# schema.net
KiCad netlist of a schematic drawn in EAGLE
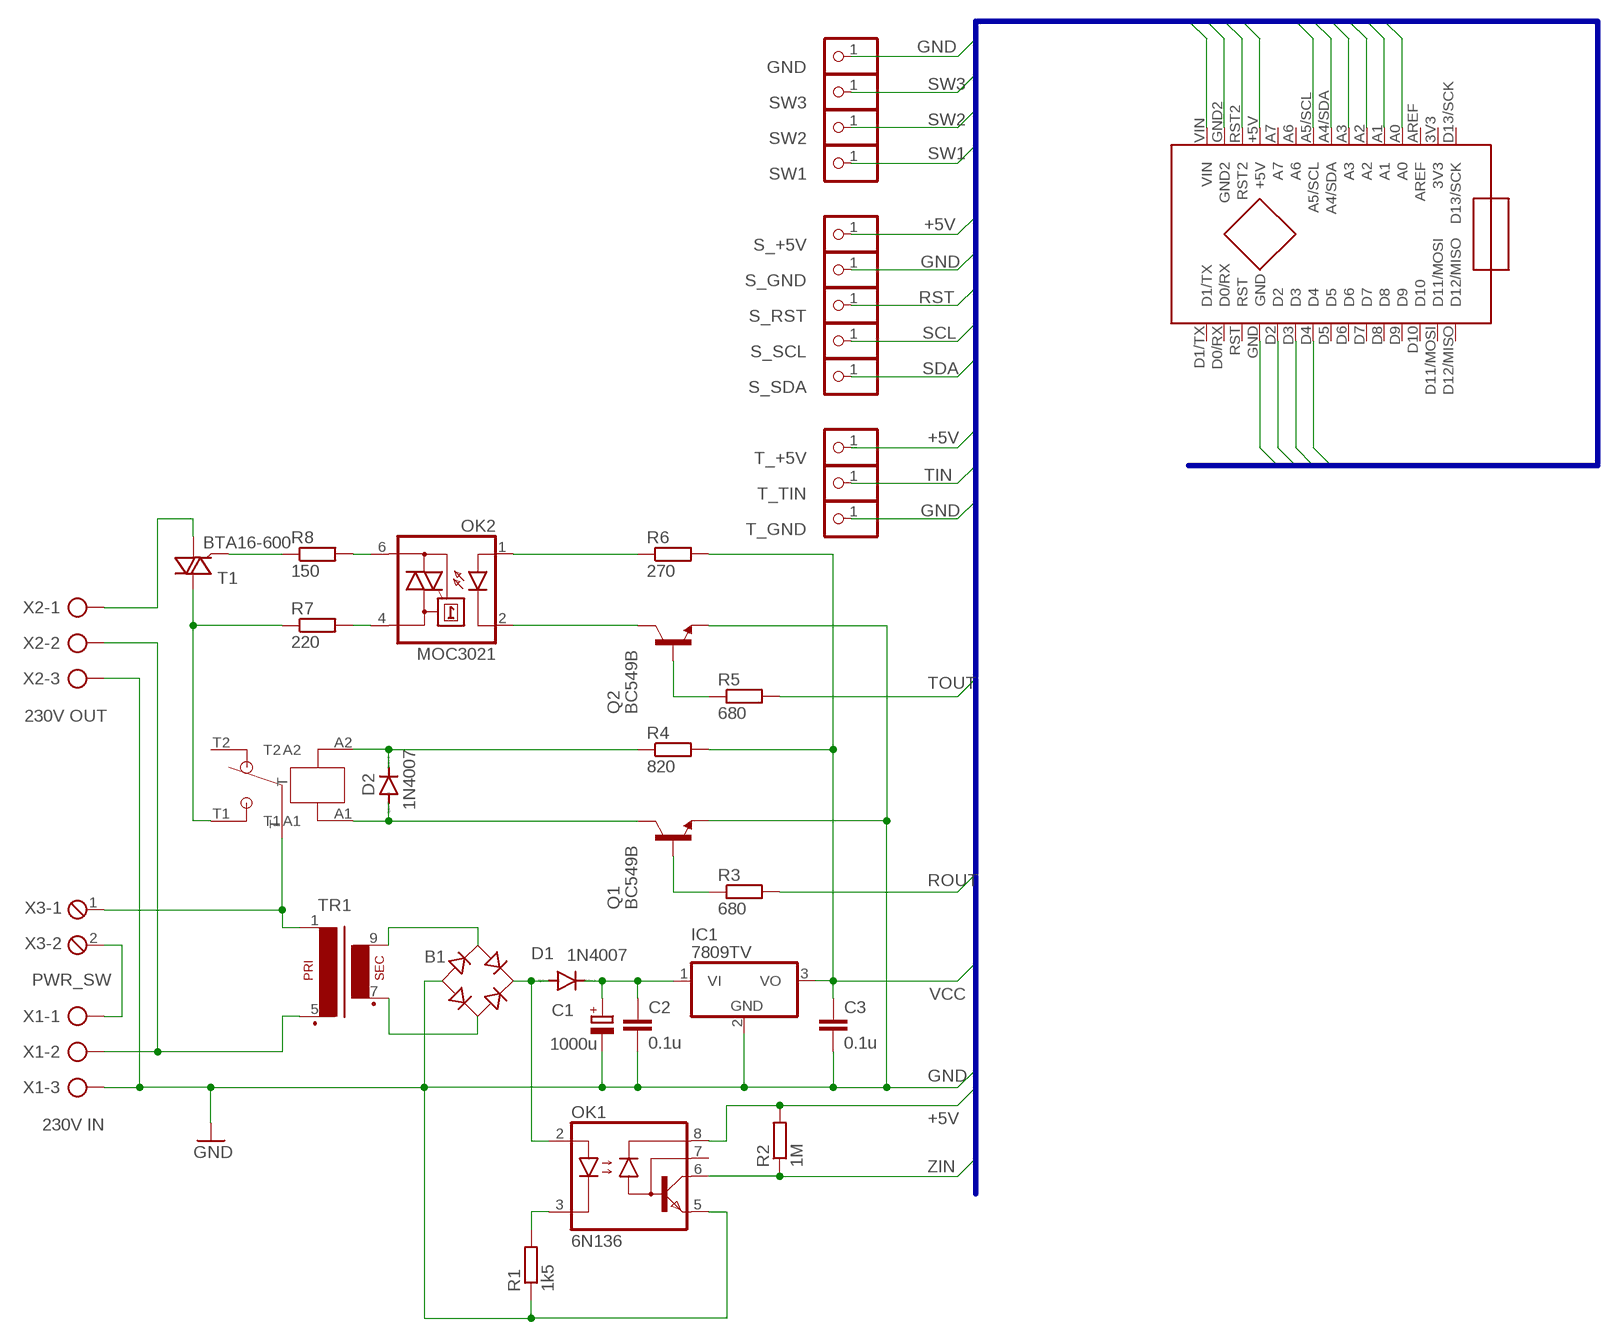
[diagram p0: schematic, sheet 1]

(export (version "E")
  (design (tool "Eeschema 10.0.6"))
  (components
    (comp (ref "B1")
      (value "B-DIL")
      (footprint "eagle-import:B-DIL")
      (libsource (lib "eagle-import") (part "B-DIL"))
    )
    (comp (ref "C1")
      (value "1000u")
      (footprint "eagle-import:E5-8,5")
      (libsource (lib "eagle-import") (part "CPOL-EUE5-8.5"))
    )
    (comp (ref "C2")
      (value "0.1u")
      (footprint "eagle-import:C050-024X044")
      (libsource (lib "eagle-import") (part "C-EU050-024X044"))
    )
    (comp (ref "C3")
      (value "0.1u")
      (footprint "eagle-import:C050-024X044")
      (libsource (lib "eagle-import") (part "C-EU050-024X044"))
    )
    (comp (ref "D1")
      (value "1N4007")
      (footprint "eagle-import:DO35-7")
      (libsource (lib "eagle-import") (part "1N4148DO35-7"))
    )
    (comp (ref "D2")
      (value "1N4007")
      (footprint "eagle-import:DO35-7")
      (libsource (lib "eagle-import") (part "1N4148DO35-7"))
    )
    (comp (ref "GND")
      (value "PINHD-1X1")
      (footprint "eagle-import:1X01")
      (libsource (lib "eagle-import") (part "PINHD-1X1"))
    )
    (comp (ref "IC1")
      (value "7809TV")
      (footprint "eagle-import:TO220V")
      (libsource (lib "eagle-import") (part "78TV05"))
    )
    (comp (ref "OK1")
      (value "6N136")
      (footprint "eagle-import:DIL08")
      (fields (field (name "MF") "FAIRCHILD SEMICONDUCTOR") (field (name "MPN") "6N135"))
      (libsource (lib "eagle-import") (part "6N135"))
    )
    (comp (ref "OK2")
      (value "MOC3021")
      (footprint "eagle-import:DIL06")
      (fields
        (field (name "MF") "FAIRCHILD SEMICONDUCTOR")
        (field (name "MPN") "MOC3041M")
        (field (name "MPN_1") "MOC3021")
      )
      (libsource (lib "eagle-import") (part "MOC3041M"))
    )
    (comp (ref "Q1")
      (value "BC549B")
      (footprint "eagle-import:TO92-EBC")
      (libsource (lib "eagle-import") (part "BC549B"))
    )
    (comp (ref "Q2")
      (value "BC549B")
      (footprint "eagle-import:TO92-EBC")
      (libsource (lib "eagle-import") (part "BC549B"))
    )
    (comp (ref "R1")
      (value "1k5")
      (footprint "eagle-import:0204V")
      (libsource (lib "eagle-import") (part "R-EU_0204/2V"))
    )
    (comp (ref "R2")
      (value "1M")
      (footprint "eagle-import:0204_5")
      (libsource (lib "eagle-import") (part "R-EU_0204/5"))
    )
    (comp (ref "R3")
      (value "680")
      (footprint "eagle-import:0204_7")
      (libsource (lib "eagle-import") (part "R-EU_0204/7"))
    )
    (comp (ref "R4")
      (value "820")
      (footprint "eagle-import:0204_7")
      (libsource (lib "eagle-import") (part "R-EU_0204/7"))
    )
    (comp (ref "R5")
      (value "680")
      (footprint "eagle-import:0204_7")
      (libsource (lib "eagle-import") (part "R-EU_0204/7"))
    )
    (comp (ref "R6")
      (value "270")
      (footprint "eagle-import:0204_7")
      (libsource (lib "eagle-import") (part "R-EU_0204/7"))
    )
    (comp (ref "R7")
      (value "220")
      (footprint "eagle-import:0204_7")
      (libsource (lib "eagle-import") (part "R-EU_0204/7"))
    )
    (comp (ref "R8")
      (value "150")
      (footprint "eagle-import:0204_7")
      (libsource (lib "eagle-import") (part "R-EU_0204/7"))
    )
    (comp (ref "SW1")
      (value "PINHD-1X1")
      (footprint "eagle-import:1X01")
      (libsource (lib "eagle-import") (part "PINHD-1X1"))
    )
    (comp (ref "SW2")
      (value "PINHD-1X1")
      (footprint "eagle-import:1X01")
      (libsource (lib "eagle-import") (part "PINHD-1X1"))
    )
    (comp (ref "SW3")
      (value "PINHD-1X1")
      (footprint "eagle-import:1X01")
      (libsource (lib "eagle-import") (part "PINHD-1X1"))
    )
    (comp (ref "S_+5V")
      (value "PINHD-1X1")
      (footprint "eagle-import:1X01")
      (libsource (lib "eagle-import") (part "PINHD-1X1"))
    )
    (comp (ref "S_GND")
      (value "PINHD-1X1")
      (footprint "eagle-import:1X01")
      (libsource (lib "eagle-import") (part "PINHD-1X1"))
    )
    (comp (ref "S_RST")
      (value "PINHD-1X1")
      (footprint "eagle-import:1X01")
      (libsource (lib "eagle-import") (part "PINHD-1X1"))
    )
    (comp (ref "S_SCL")
      (value "PINHD-1X1")
      (footprint "eagle-import:1X01")
      (libsource (lib "eagle-import") (part "PINHD-1X1"))
    )
    (comp (ref "S_SDA")
      (value "PINHD-1X1")
      (footprint "eagle-import:1X01")
      (libsource (lib "eagle-import") (part "PINHD-1X1"))
    )
    (comp (ref "T1")
      (value "BTA16-600")
      (footprint "eagle-import:TO220BV")
      (libsource (lib "eagle-import") (part "BT138-V"))
    )
    (comp (ref "TR1")
      (value "EI30-1")
      (footprint "eagle-import:EI30-1")
      (libsource (lib "eagle-import") (part "EI30-1"))
    )
    (comp (ref "T_+5V")
      (value "PINHD-1X1")
      (footprint "eagle-import:1X01")
      (libsource (lib "eagle-import") (part "PINHD-1X1"))
    )
    (comp (ref "T_GND")
      (value "PINHD-1X1")
      (footprint "eagle-import:1X01")
      (libsource (lib "eagle-import") (part "PINHD-1X1"))
    )
    (comp (ref "T_TIN")
      (value "PINHD-1X1")
      (footprint "eagle-import:1X01")
      (libsource (lib "eagle-import") (part "PINHD-1X1"))
    )
    (comp (ref "U$1")
      (value "FINDER_31.21.X")
      (footprint "eagle-import:FINDER_32.21.X")
      (libsource (lib "eagle-import") (part "FINDER_31.21.X"))
    )
    (comp (ref "U$2")
      (value "ARDUINO_NANO")
      (footprint "eagle-import:ARDUINO_NANO")
      (libsource (lib "eagle-import") (part "ARDUINO_NANO"))
    )
    (comp (ref "X1")
      (value "230V IN")
      (footprint "eagle-import:AK500_3")
      (libsource (lib "eagle-import") (part "AK500/3"))
    )
    (comp (ref "X2")
      (value "230V OUT")
      (footprint "eagle-import:AK500_3")
      (libsource (lib "eagle-import") (part "AK500/3"))
    )
    (comp (ref "X3")
      (value "PWR_SW")
      (footprint "eagle-import:2POL254")
      (libsource (lib "eagle-import") (part "MPT2"))
    )
  )
  (nets
    (net (code "1") (name "/+5V") (class "Default")
      (node (ref "OK1") (pin "8") (pinfunction "VCC_8") (pintype "passive"))
      (node (ref "R2") (pin "2") (pinfunction "2_2") (pintype "passive"))
      (node (ref "S_+5V") (pin "1") (pinfunction "1_1") (pintype "passive"))
      (node (ref "T_+5V") (pin "1") (pinfunction "1_1") (pintype "passive"))
      (node (ref "U$2") (pin "+5V") (pinfunction "+5V_+5V") (pintype "bidirectional"))
    )
    (net (code "2") (name "/ROUT") (class "Default")
      (node (ref "R3") (pin "2") (pinfunction "2_2") (pintype "passive"))
      (node (ref "U$2") (pin "A1") (pinfunction "A1_A1") (pintype "bidirectional"))
    )
    (net (code "3") (name "/RST") (class "Default")
      (node (ref "S_RST") (pin "1") (pinfunction "1_1") (pintype "passive"))
      (node (ref "U$2") (pin "RST2") (pinfunction "RST2_RST2") (pintype "bidirectional"))
    )
    (net (code "4") (name "/SCL") (class "Default")
      (node (ref "S_SCL") (pin "1") (pinfunction "1_1") (pintype "passive"))
      (node (ref "U$2") (pin "A5/SCL") (pinfunction "A5/SCL_A5/SCL") (pintype "bidirectional"))
    )
    (net (code "5") (name "/SDA") (class "Default")
      (node (ref "S_SDA") (pin "1") (pinfunction "1_1") (pintype "passive"))
      (node (ref "U$2") (pin "A4/SDA") (pinfunction "A4/SDA_A4/SDA") (pintype "bidirectional"))
    )
    (net (code "6") (name "/SW1") (class "Default")
      (node (ref "SW1") (pin "1") (pinfunction "1_1") (pintype "passive"))
      (node (ref "U$2") (pin "D2") (pinfunction "D2_D2") (pintype "bidirectional"))
    )
    (net (code "7") (name "/SW2") (class "Default")
      (node (ref "SW2") (pin "1") (pinfunction "1_1") (pintype "passive"))
      (node (ref "U$2") (pin "D3") (pinfunction "D3_D3") (pintype "bidirectional"))
    )
    (net (code "8") (name "/SW3") (class "Default")
      (node (ref "SW3") (pin "1") (pinfunction "1_1") (pintype "passive"))
      (node (ref "U$2") (pin "D4") (pinfunction "D4_D4") (pintype "bidirectional"))
    )
    (net (code "9") (name "/TIN") (class "Default")
      (node (ref "T_TIN") (pin "1") (pinfunction "1_1") (pintype "passive"))
      (node (ref "U$2") (pin "A2") (pinfunction "A2_A2") (pintype "bidirectional"))
    )
    (net (code "10") (name "/TOUT") (class "Default")
      (node (ref "R5") (pin "2") (pinfunction "2_2") (pintype "passive"))
      (node (ref "U$2") (pin "A0") (pinfunction "A0_A0") (pintype "bidirectional"))
    )
    (net (code "11") (name "/VCC") (class "Default")
      (node (ref "C3") (pin "1") (pinfunction "1_1") (pintype "passive"))
      (node (ref "IC1") (pin "3") (pinfunction "VO_3") (pintype "passive"))
      (node (ref "R4") (pin "2") (pinfunction "2_2") (pintype "passive"))
      (node (ref "R6") (pin "2") (pinfunction "2_2") (pintype "passive"))
      (node (ref "U$2") (pin "VIN") (pinfunction "VIN_VIN") (pintype "bidirectional"))
    )
    (net (code "12") (name "/ZIN") (class "Default")
      (node (ref "OK1") (pin "6") (pinfunction "VO_6") (pintype "passive"))
      (node (ref "R2") (pin "1") (pinfunction "1_1") (pintype "passive"))
      (node (ref "U$2") (pin "A3") (pinfunction "A3_A3") (pintype "bidirectional"))
    )
    (net (code "13") (name "GND") (class "Default")
      (node (ref "B1") (pin "-") (pinfunction "-_-") (pintype "passive"))
      (node (ref "C1") (pin "-") (pinfunction "-_-") (pintype "passive"))
      (node (ref "C2") (pin "2") (pinfunction "2_2") (pintype "passive"))
      (node (ref "C3") (pin "2") (pinfunction "2_2") (pintype "passive"))
      (node (ref "GND") (pin "1") (pinfunction "1_1") (pintype "passive"))
      (node (ref "IC1") (pin "2") (pinfunction "GND_2") (pintype "passive"))
      (node (ref "OK1") (pin "5") (pinfunction "GND_5") (pintype "passive"))
      (node (ref "Q1") (pin "E") (pinfunction "E_E") (pintype "passive"))
      (node (ref "Q2") (pin "E") (pinfunction "E_E") (pintype "passive"))
      (node (ref "R1") (pin "1") (pinfunction "1_1") (pintype "passive"))
      (node (ref "S_GND") (pin "1") (pinfunction "1_1") (pintype "passive"))
      (node (ref "T_GND") (pin "1") (pinfunction "1_1") (pintype "passive"))
      (node (ref "U$2") (pin "GND") (pinfunction "GND_GND") (pintype "bidirectional"))
      (node (ref "U$2") (pin "GND2") (pinfunction "GND2_GND2") (pintype "bidirectional"))
      (node (ref "X1") (pin "3") (pinfunction "KL_3") (pintype "passive"))
      (node (ref "X2") (pin "3") (pinfunction "KL_3") (pintype "passive"))
    )
    (net (code "14") (name "Net-(D2-PadA)") (class "Default")
      (node (ref "D2") (pin "A") (pinfunction "A_A") (pintype "passive"))
      (node (ref "Q1") (pin "C") (pinfunction "C_C") (pintype "passive"))
      (node (ref "U$1") (pin "A1") (pinfunction "A1_A1") (pintype "bidirectional"))
    )
    (net (code "15") (name "Net-(D2-PadC)") (class "Default")
      (node (ref "D2") (pin "C") (pinfunction "C_C") (pintype "passive"))
      (node (ref "R4") (pin "1") (pinfunction "1_1") (pintype "passive"))
      (node (ref "U$1") (pin "A2") (pinfunction "A2_A2") (pintype "bidirectional"))
    )
    (net (code "16") (name "Net-(IC1-VI)") (class "Default")
      (node (ref "C1") (pin "+") (pinfunction "+_+") (pintype "passive"))
      (node (ref "C2") (pin "1") (pinfunction "1_1") (pintype "passive"))
      (node (ref "D1") (pin "C") (pinfunction "C_C") (pintype "passive"))
      (node (ref "IC1") (pin "1") (pinfunction "VI_1") (pintype "input"))
    )
    (net (code "17") (name "Net-(OK1-A)") (class "Default")
      (node (ref "B1") (pin "+") (pinfunction "+_+") (pintype "passive"))
      (node (ref "D1") (pin "A") (pinfunction "A_A") (pintype "passive"))
      (node (ref "OK1") (pin "2") (pinfunction "A_2") (pintype "passive"))
    )
    (net (code "18") (name "Net-(OK1-C)") (class "Default")
      (node (ref "OK1") (pin "3") (pinfunction "C_3") (pintype "passive"))
      (node (ref "R1") (pin "2") (pinfunction "2_2") (pintype "passive"))
    )
    (net (code "19") (name "Net-(OK2-A)") (class "Default")
      (node (ref "OK2") (pin "1") (pinfunction "A_1") (pintype "passive"))
      (node (ref "R6") (pin "1") (pinfunction "1_1") (pintype "passive"))
    )
    (net (code "20") (name "Net-(OK2-A1)") (class "Default")
      (node (ref "OK2") (pin "4") (pinfunction "A1_4") (pintype "passive"))
      (node (ref "R7") (pin "2") (pinfunction "2_2") (pintype "passive"))
    )
    (net (code "21") (name "Net-(OK2-A2)") (class "Default")
      (node (ref "OK2") (pin "6") (pinfunction "A2_6") (pintype "passive"))
      (node (ref "R8") (pin "2") (pinfunction "2_2") (pintype "passive"))
    )
    (net (code "22") (name "Net-(OK2-C)") (class "Default")
      (node (ref "OK2") (pin "2") (pinfunction "C_2") (pintype "passive"))
      (node (ref "Q2") (pin "C") (pinfunction "C_C") (pintype "passive"))
    )
    (net (code "23") (name "Net-(Q1-PadB)") (class "Default")
      (node (ref "Q1") (pin "B") (pinfunction "B_B") (pintype "passive"))
      (node (ref "R3") (pin "1") (pinfunction "1_1") (pintype "passive"))
    )
    (net (code "24") (name "Net-(Q2-PadB)") (class "Default")
      (node (ref "Q2") (pin "B") (pinfunction "B_B") (pintype "passive"))
      (node (ref "R5") (pin "1") (pinfunction "1_1") (pintype "passive"))
    )
    (net (code "25") (name "Net-(R8-Pad1)") (class "Default")
      (node (ref "R8") (pin "1") (pinfunction "1_1") (pintype "passive"))
      (node (ref "T1") (pin "G") (pinfunction "G_G") (pintype "passive"))
    )
    (net (code "26") (name "Net-(T1-A1)") (class "Default")
      (node (ref "T1") (pin "T1") (pinfunction "A1_T1") (pintype "passive"))
      (node (ref "X2") (pin "1") (pinfunction "KL_1") (pintype "passive"))
    )
    (net (code "27") (name "Net-(T1-A2)") (class "Default")
      (node (ref "R7") (pin "1") (pinfunction "1_1") (pintype "passive"))
      (node (ref "T1") (pin "T2") (pinfunction "A2_T2") (pintype "passive"))
      (node (ref "U$1") (pin "T1") (pinfunction "T1_T1") (pintype "bidirectional"))
    )
    (net (code "28") (name "Net-(TR1-P1)") (class "Default")
      (node (ref "TR1") (pin "1") (pinfunction "P1_1") (pintype "passive"))
      (node (ref "U$1") (pin "T") (pinfunction "T_T") (pintype "bidirectional"))
      (node (ref "X3") (pin "1") (pinfunction "1_1") (pintype "passive"))
    )
    (net (code "29") (name "Net-(TR1-P2)") (class "Default")
      (node (ref "TR1") (pin "5") (pinfunction "P2_5") (pintype "passive"))
      (node (ref "X1") (pin "2") (pinfunction "KL_2") (pintype "passive"))
      (node (ref "X2") (pin "2") (pinfunction "KL_2") (pintype "passive"))
    )
    (net (code "30") (name "Net-(TR1-S3)") (class "Default")
      (node (ref "B1") (pin "AC2") (pinfunction "AC2_AC2") (pintype "passive"))
      (node (ref "TR1") (pin "7") (pinfunction "S3_7") (pintype "passive"))
    )
    (net (code "31") (name "Net-(TR1-S4)") (class "Default")
      (node (ref "B1") (pin "AC1") (pinfunction "AC1_AC1") (pintype "passive"))
      (node (ref "TR1") (pin "9") (pinfunction "S4_9") (pintype "passive"))
    )
    (net (code "32") (name "Net-(X1A-KL)") (class "Default")
      (node (ref "X1") (pin "1") (pinfunction "KL_1") (pintype "passive"))
      (node (ref "X3") (pin "2") (pinfunction "1_2") (pintype "passive"))
    )
    (net (code "33") (name "unconnected-(OK1-VB-Pad7)") (class "Default")
      (node (ref "OK1") (pin "7") (pinfunction "VB_7") (pintype "passive"))
    )
    (net (code "34") (name "unconnected-(U$1-PadT2)") (class "Default")
      (node (ref "U$1") (pin "T2") (pinfunction "T2_T2") (pintype "bidirectional"))
    )
    (net (code "35") (name "unconnected-(U$2-Pad3V3)") (class "Default")
      (node (ref "U$2") (pin "3V3") (pinfunction "3V3_3V3") (pintype "bidirectional"))
    )
    (net (code "36") (name "unconnected-(U$2-PadA6)") (class "Default")
      (node (ref "U$2") (pin "A6") (pinfunction "A6_A6") (pintype "bidirectional"))
    )
    (net (code "37") (name "unconnected-(U$2-PadA7)") (class "Default")
      (node (ref "U$2") (pin "A7") (pinfunction "A7_A7") (pintype "bidirectional"))
    )
    (net (code "38") (name "unconnected-(U$2-PadAREF)") (class "Default")
      (node (ref "U$2") (pin "AREF") (pinfunction "AREF_AREF") (pintype "bidirectional"))
    )
    (net (code "39") (name "unconnected-(U$2-PadD0{slash}RX)") (class "Default")
      (node (ref "U$2") (pin "D0/RX") (pinfunction "D0/RX_D0/RX") (pintype "bidirectional"))
    )
    (net (code "40") (name "unconnected-(U$2-PadD1{slash}TX)") (class "Default")
      (node (ref "U$2") (pin "D1/TX") (pinfunction "D1/TX_D1/TX") (pintype "bidirectional"))
    )
    (net (code "41") (name "unconnected-(U$2-PadD5)") (class "Default")
      (node (ref "U$2") (pin "D5") (pinfunction "D5_D5") (pintype "bidirectional"))
    )
    (net (code "42") (name "unconnected-(U$2-PadD6)") (class "Default")
      (node (ref "U$2") (pin "D6") (pinfunction "D6_D6") (pintype "bidirectional"))
    )
    (net (code "43") (name "unconnected-(U$2-PadD7)") (class "Default")
      (node (ref "U$2") (pin "D7") (pinfunction "D7_D7") (pintype "bidirectional"))
    )
    (net (code "44") (name "unconnected-(U$2-PadD8)") (class "Default")
      (node (ref "U$2") (pin "D8") (pinfunction "D8_D8") (pintype "bidirectional"))
    )
    (net (code "45") (name "unconnected-(U$2-PadD9)") (class "Default")
      (node (ref "U$2") (pin "D9") (pinfunction "D9_D9") (pintype "bidirectional"))
    )
    (net (code "46") (name "unconnected-(U$2-PadD10)") (class "Default")
      (node (ref "U$2") (pin "D10") (pinfunction "D10_D10") (pintype "bidirectional"))
    )
    (net (code "47") (name "unconnected-(U$2-PadD11{slash}MOSI)") (class "Default")
      (node (ref "U$2") (pin "D11/MOSI") (pinfunction "D11/MOSI_D11/MOSI") (pintype "bidirectional"))
    )
    (net (code "48") (name "unconnected-(U$2-PadD12{slash}MISO)") (class "Default")
      (node (ref "U$2") (pin "D12/MISO") (pinfunction "D12/MISO_D12/MISO") (pintype "bidirectional"))
    )
    (net (code "49") (name "unconnected-(U$2-PadD13{slash}SCK)") (class "Default")
      (node (ref "U$2") (pin "D13/SCK") (pinfunction "D13/SCK_D13/SCK") (pintype "bidirectional"))
    )
    (net (code "50") (name "unconnected-(U$2-PadRST)") (class "Default")
      (node (ref "U$2") (pin "RST") (pinfunction "RST_RST") (pintype "bidirectional"))
    )
  )
)
